# usbswitch.net
KiCad netlist of a schematic drawn in EAGLE
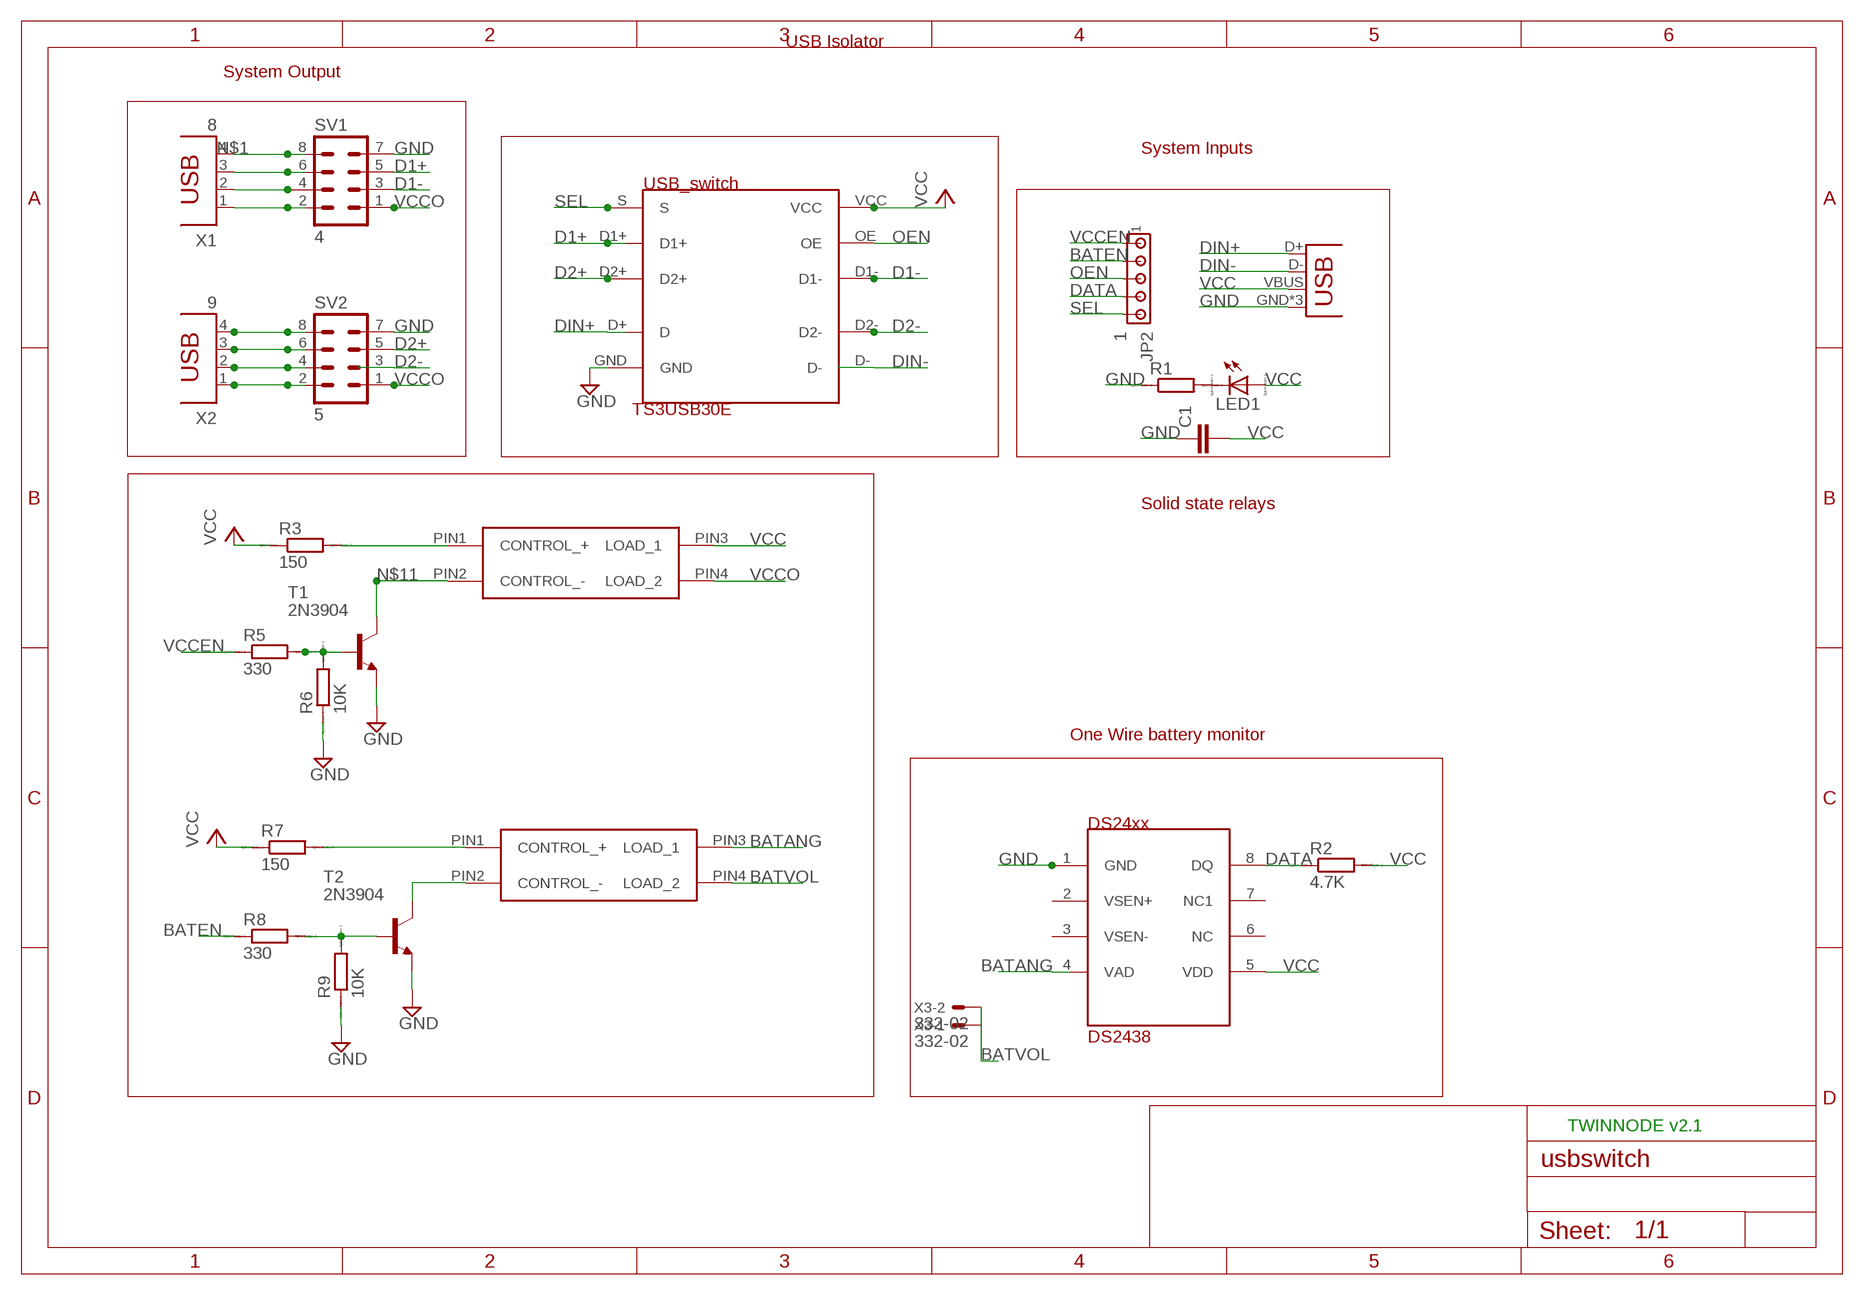
[diagram p0: schematic, sheet 1]

(export (version "E")
  (design (tool "Eeschema 10.0.6"))
  (components
    (comp (ref "C1")
      (value "C2.5/6")
      (footprint "eagle-import:C2.5-6")
      (libsource (lib "eagle-import") (part "C2.5/6"))
    )
    (comp (ref "JP1")
      (value "USB-MICROB")
      (footprint "eagle-import:USB-MICROB")
      (libsource (lib "eagle-import") (part "USB-MICROB"))
    )
    (comp (ref "JP2")
      (value "1")
      (footprint "eagle-import:10X05MTA")
      (libsource (lib "eagle-import") (part "MTA05-100"))
    )
    (comp (ref "LED1")
      (value "LED_ELD260")
      (footprint "eagle-import:LED_LD260")
      (libsource (lib "eagle-import") (part "LED_ELD260"))
    )
    (comp (ref "R1")
      (value "RR3216")
      (footprint "eagle-import:R3216")
      (libsource (lib "eagle-import") (part "RR3216"))
    )
    (comp (ref "R2")
      (value "4.7K")
      (footprint "eagle-import:R3216")
      (libsource (lib "eagle-import") (part "RR3216"))
    )
    (comp (ref "R3")
      (value "150")
      (footprint "eagle-import:R3216")
      (libsource (lib "eagle-import") (part "RR3216"))
    )
    (comp (ref "R5")
      (value "330")
      (footprint "eagle-import:R3216")
      (libsource (lib "eagle-import") (part "RR3216"))
    )
    (comp (ref "R6")
      (value "10K")
      (footprint "eagle-import:R3216")
      (libsource (lib "eagle-import") (part "RR3216"))
    )
    (comp (ref "R7")
      (value "150")
      (footprint "eagle-import:R3216")
      (libsource (lib "eagle-import") (part "RR3216"))
    )
    (comp (ref "R8")
      (value "330")
      (footprint "eagle-import:R3216")
      (libsource (lib "eagle-import") (part "RR3216"))
    )
    (comp (ref "R9")
      (value "10K")
      (footprint "eagle-import:R3216")
      (libsource (lib "eagle-import") (part "RR3216"))
    )
    (comp (ref "SV1")
      (value "4")
      (footprint "eagle-import:MA04-2")
      (libsource (lib "eagle-import") (part "MA04-2"))
    )
    (comp (ref "SV2")
      (value "5")
      (footprint "eagle-import:MA04-2")
      (libsource (lib "eagle-import") (part "MA04-2"))
    )
    (comp (ref "T1")
      (value "2N3904")
      (footprint "eagle-import:TO92")
      (libsource (lib "eagle-import") (part "2N3904"))
    )
    (comp (ref "T2")
      (value "2N3904")
      (footprint "eagle-import:TO92")
      (libsource (lib "eagle-import") (part "2N3904"))
    )
    (comp (ref "U$1")
      (value "USB_SWITCH")
      (footprint "eagle-import:PDSO-G10")
      (libsource (lib "eagle-import") (part "myusbswitch_USB_SWITCH"))
    )
    (comp (ref "U$2")
      (value "DS2438")
      (footprint "eagle-import:DS243PKG")
      (libsource (lib "eagle-import") (part "DS2438"))
    )
    (comp (ref "U$3")
      (value "OPTO-RELAY-CPC1017N")
      (footprint "eagle-import:SOP-4")
      (libsource (lib "eagle-import") (part "OPTO-RELAY-CPC1017N"))
    )
    (comp (ref "U$4")
      (value "OPTO-RELAY-CPC1017N")
      (footprint "eagle-import:SOP-4")
      (libsource (lib "eagle-import") (part "OPTO-RELAY-CPC1017N"))
    )
    (comp (ref "X1")
      (value "8")
      (footprint "eagle-import:PN87520")
      (libsource (lib "eagle-import") (part "PN87520"))
    )
    (comp (ref "X2")
      (value "9")
      (footprint "eagle-import:PN87520")
      (libsource (lib "eagle-import") (part "PN87520"))
    )
    (comp (ref "X3")
      (value "332-02")
      (footprint "eagle-import:332-02")
      (libsource (lib "eagle-import") (part "332-02"))
    )
  )
  (nets
    (net (code "1") (name "/BATANG") (class "Default")
      (node (ref "U$2") (pin "4") (pinfunction "VAD_4") (pintype "bidirectional"))
      (node (ref "U$3") (pin "PIN3") (pinfunction "LOAD_1_PIN3") (pintype "bidirectional"))
    )
    (net (code "2") (name "/BATEN") (class "Default")
      (node (ref "JP2") (pin "2") (pinfunction "2_2") (pintype "passive"))
      (node (ref "R8") (pin "1") (pinfunction "1_1") (pintype "passive"))
    )
    (net (code "3") (name "/BATVOL") (class "Default")
      (node (ref "U$3") (pin "PIN4") (pinfunction "LOAD_2_PIN4") (pintype "bidirectional"))
      (node (ref "X3") (pin "1") (pinfunction "S_1") (pintype "passive"))
      (node (ref "X3") (pin "2") (pinfunction "S_2") (pintype "passive"))
    )
    (net (code "4") (name "/D1+") (class "Default")
      (node (ref "SV1") (pin "5") (pinfunction "5_5") (pintype "passive"))
      (node (ref "U$1") (pin "D1+") (pinfunction "D1+_D1+") (pintype "bidirectional"))
    )
    (net (code "5") (name "/D1-") (class "Default")
      (node (ref "SV1") (pin "3") (pinfunction "3_3") (pintype "passive"))
      (node (ref "U$1") (pin "D1-") (pinfunction "D1-_D1-") (pintype "bidirectional"))
    )
    (net (code "6") (name "/D2+") (class "Default")
      (node (ref "SV2") (pin "5") (pinfunction "5_5") (pintype "passive"))
      (node (ref "U$1") (pin "D2+") (pinfunction "D2+_D2+") (pintype "bidirectional"))
    )
    (net (code "7") (name "/D2-") (class "Default")
      (node (ref "SV2") (pin "3") (pinfunction "3_3") (pintype "passive"))
      (node (ref "U$1") (pin "D2-") (pinfunction "D2-_D2-") (pintype "bidirectional"))
    )
    (net (code "8") (name "/DATA") (class "Default")
      (node (ref "JP2") (pin "4") (pinfunction "4_4") (pintype "passive"))
      (node (ref "R2") (pin "1") (pinfunction "1_1") (pintype "passive"))
      (node (ref "U$2") (pin "8") (pinfunction "DQ_8") (pintype "bidirectional"))
    )
    (net (code "9") (name "/DIN+") (class "Default")
      (node (ref "JP1") (pin "D+") (pinfunction "D+_D+") (pintype "bidirectional"))
      (node (ref "U$1") (pin "D+") (pinfunction "D_D+") (pintype "bidirectional"))
    )
    (net (code "10") (name "/DIN-") (class "Default")
      (node (ref "JP1") (pin "D-") (pinfunction "D-_D-") (pintype "bidirectional"))
      (node (ref "U$1") (pin "D-") (pinfunction "D-_D-") (pintype "bidirectional"))
    )
    (net (code "11") (name "/N$1") (class "Default")
      (node (ref "SV1") (pin "8") (pinfunction "8_8") (pintype "passive"))
      (node (ref "X1") (pin "4") (pinfunction "4_4") (pintype "passive"))
    )
    (net (code "12") (name "/N$11") (class "Default")
      (node (ref "T1") (pin "1") (pinfunction "C_1") (pintype "passive"))
      (node (ref "U$4") (pin "PIN2") (pinfunction "CONTROL_-_PIN2") (pintype "bidirectional"))
    )
    (net (code "13") (name "/OEN") (class "Default")
      (node (ref "JP2") (pin "3") (pinfunction "3_3") (pintype "passive"))
      (node (ref "U$1") (pin "OE") (pinfunction "OE_OE") (pintype "bidirectional"))
    )
    (net (code "14") (name "/SEL") (class "Default")
      (node (ref "JP2") (pin "5") (pinfunction "5_5") (pintype "passive"))
      (node (ref "U$1") (pin "S") (pinfunction "S_S") (pintype "bidirectional"))
    )
    (net (code "15") (name "/VCCEN") (class "Default")
      (node (ref "JP2") (pin "1") (pinfunction "1_1") (pintype "passive"))
      (node (ref "R5") (pin "1") (pinfunction "1_1") (pintype "passive"))
    )
    (net (code "16") (name "/VCCO") (class "Default")
      (node (ref "SV1") (pin "1") (pinfunction "1_1") (pintype "passive"))
      (node (ref "SV2") (pin "1") (pinfunction "1_1") (pintype "passive"))
      (node (ref "U$4") (pin "PIN4") (pinfunction "LOAD_2_PIN4") (pintype "bidirectional"))
    )
    (net (code "17") (name "GND") (class "Default")
      (node (ref "C1") (pin "1") (pinfunction "1_1") (pintype "passive"))
      (node (ref "JP1") (pin "GND") (pinfunction "GND_GND") (pintype "bidirectional"))
      (node (ref "JP1") (pin "MT1") (pinfunction "GND_MT1") (pintype "bidirectional"))
      (node (ref "JP1") (pin "MT2") (pinfunction "GND_MT2") (pintype "bidirectional"))
      (node (ref "R1") (pin "1") (pinfunction "1_1") (pintype "passive"))
      (node (ref "R6") (pin "1") (pinfunction "1_1") (pintype "passive"))
      (node (ref "R9") (pin "1") (pinfunction "1_1") (pintype "passive"))
      (node (ref "SV1") (pin "7") (pinfunction "7_7") (pintype "passive"))
      (node (ref "SV2") (pin "7") (pinfunction "7_7") (pintype "passive"))
      (node (ref "T1") (pin "3") (pinfunction "E_3") (pintype "passive"))
      (node (ref "T2") (pin "3") (pinfunction "E_3") (pintype "passive"))
      (node (ref "U$1") (pin "GND") (pinfunction "GND_GND") (pintype "bidirectional"))
      (node (ref "U$2") (pin "1") (pinfunction "GND_1") (pintype "bidirectional"))
    )
    (net (code "18") (name "Net-(LED1-C)") (class "Default")
      (node (ref "LED1") (pin "K") (pinfunction "C_K") (pintype "passive"))
      (node (ref "R1") (pin "2") (pinfunction "2_2") (pintype "passive"))
    )
    (net (code "19") (name "Net-(SV1-Pad2)") (class "Default")
      (node (ref "SV1") (pin "2") (pinfunction "2_2") (pintype "passive"))
      (node (ref "X1") (pin "1") (pinfunction "1_1") (pintype "passive"))
    )
    (net (code "20") (name "Net-(SV1-Pad4)") (class "Default")
      (node (ref "SV1") (pin "4") (pinfunction "4_4") (pintype "passive"))
      (node (ref "X1") (pin "2") (pinfunction "2_2") (pintype "passive"))
    )
    (net (code "21") (name "Net-(SV1-Pad6)") (class "Default")
      (node (ref "SV1") (pin "6") (pinfunction "6_6") (pintype "passive"))
      (node (ref "X1") (pin "3") (pinfunction "3_3") (pintype "passive"))
    )
    (net (code "22") (name "Net-(SV2-Pad2)") (class "Default")
      (node (ref "SV2") (pin "2") (pinfunction "2_2") (pintype "passive"))
      (node (ref "X2") (pin "1") (pinfunction "1_1") (pintype "passive"))
    )
    (net (code "23") (name "Net-(SV2-Pad4)") (class "Default")
      (node (ref "SV2") (pin "4") (pinfunction "4_4") (pintype "passive"))
      (node (ref "X2") (pin "2") (pinfunction "2_2") (pintype "passive"))
    )
    (net (code "24") (name "Net-(SV2-Pad6)") (class "Default")
      (node (ref "SV2") (pin "6") (pinfunction "6_6") (pintype "passive"))
      (node (ref "X2") (pin "3") (pinfunction "3_3") (pintype "passive"))
    )
    (net (code "25") (name "Net-(SV2-Pad8)") (class "Default")
      (node (ref "SV2") (pin "8") (pinfunction "8_8") (pintype "passive"))
      (node (ref "X2") (pin "4") (pinfunction "4_4") (pintype "passive"))
    )
    (net (code "26") (name "Net-(T1-B)") (class "Default")
      (node (ref "R5") (pin "2") (pinfunction "2_2") (pintype "passive"))
      (node (ref "R6") (pin "2") (pinfunction "2_2") (pintype "passive"))
      (node (ref "T1") (pin "2") (pinfunction "B_2") (pintype "passive"))
    )
    (net (code "27") (name "Net-(T2-B)") (class "Default")
      (node (ref "R8") (pin "2") (pinfunction "2_2") (pintype "passive"))
      (node (ref "R9") (pin "2") (pinfunction "2_2") (pintype "passive"))
      (node (ref "T2") (pin "2") (pinfunction "B_2") (pintype "passive"))
    )
    (net (code "28") (name "Net-(T2-C)") (class "Default")
      (node (ref "T2") (pin "1") (pinfunction "C_1") (pintype "passive"))
      (node (ref "U$3") (pin "PIN2") (pinfunction "CONTROL_-_PIN2") (pintype "bidirectional"))
    )
    (net (code "29") (name "Net-(U$3-CONTROL_+)") (class "Default")
      (node (ref "R7") (pin "2") (pinfunction "2_2") (pintype "passive"))
      (node (ref "U$3") (pin "PIN1") (pinfunction "CONTROL_+_PIN1") (pintype "bidirectional"))
    )
    (net (code "30") (name "Net-(U$4-CONTROL_+)") (class "Default")
      (node (ref "R3") (pin "2") (pinfunction "2_2") (pintype "passive"))
      (node (ref "U$4") (pin "PIN1") (pinfunction "CONTROL_+_PIN1") (pintype "bidirectional"))
    )
    (net (code "31") (name "VCC") (class "Default")
      (node (ref "C1") (pin "2") (pinfunction "2_2") (pintype "passive"))
      (node (ref "JP1") (pin "VBUS") (pinfunction "VBUS_VBUS") (pintype "bidirectional"))
      (node (ref "LED1") (pin "A") (pinfunction "A_A") (pintype "passive"))
      (node (ref "R2") (pin "2") (pinfunction "2_2") (pintype "passive"))
      (node (ref "R3") (pin "1") (pinfunction "1_1") (pintype "passive"))
      (node (ref "R7") (pin "1") (pinfunction "1_1") (pintype "passive"))
      (node (ref "U$1") (pin "VCC") (pinfunction "VCC_VCC") (pintype "bidirectional"))
      (node (ref "U$2") (pin "5") (pinfunction "VDD_5") (pintype "bidirectional"))
      (node (ref "U$4") (pin "PIN3") (pinfunction "LOAD_1_PIN3") (pintype "bidirectional"))
    )
    (net (code "32") (name "unconnected-(U$2-NC-Pad6)") (class "Default")
      (node (ref "U$2") (pin "6") (pinfunction "NC_6") (pintype "bidirectional"))
    )
    (net (code "33") (name "unconnected-(U$2-NC1-Pad7)") (class "Default")
      (node (ref "U$2") (pin "7") (pinfunction "NC1_7") (pintype "bidirectional"))
    )
    (net (code "34") (name "unconnected-(U$2-VSEN+-Pad2)") (class "Default")
      (node (ref "U$2") (pin "2") (pinfunction "VSEN+_2") (pintype "bidirectional"))
    )
    (net (code "35") (name "unconnected-(U$2-VSEN--Pad3)") (class "Default")
      (node (ref "U$2") (pin "3") (pinfunction "VSEN-_3") (pintype "bidirectional"))
    )
  )
)
